# mechanical.net
KiCad netlist of a schematic drawn in Altium Designer
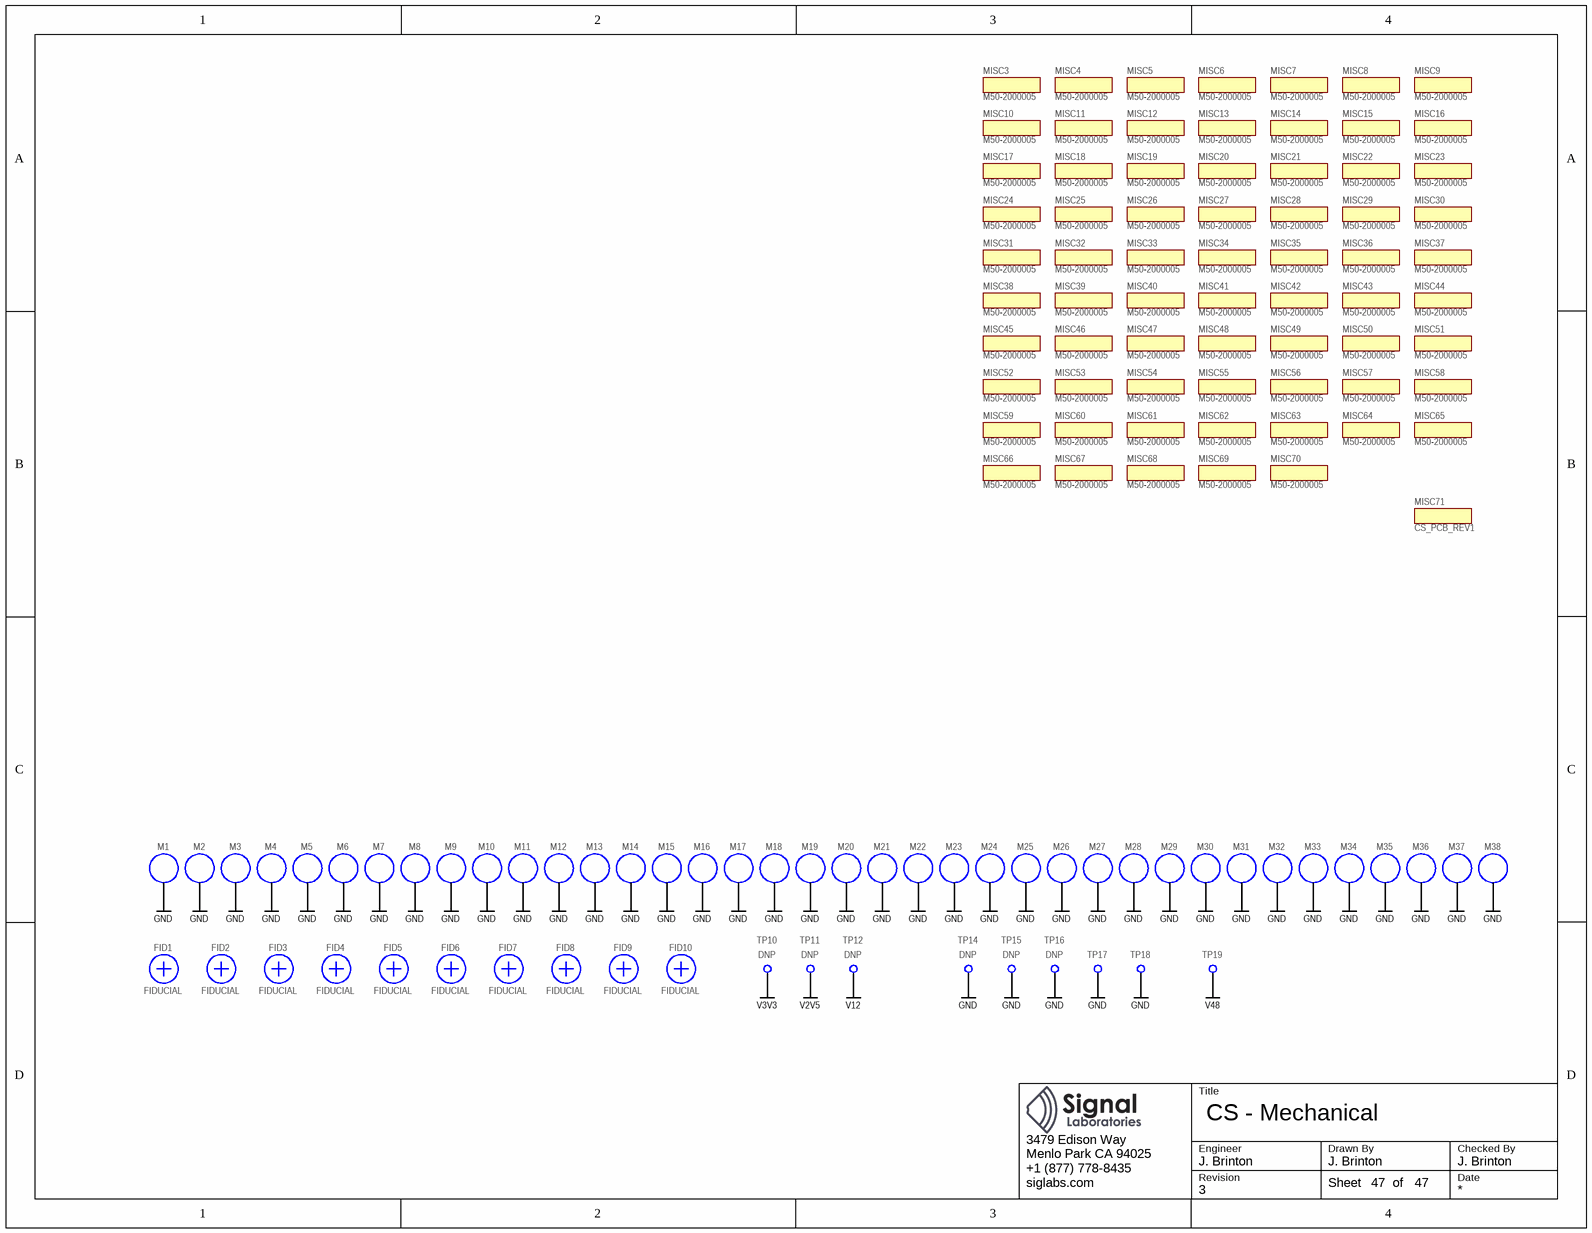
[diagram p0: mechanical.SchDoc]

(export (version "E")
  (design (tool "Eeschema 10.0.6"))
  (components
    (comp (ref "FID1")
      (value "FIDUCIAL")
      (footprint "FIDUCIAL")
      (libsource (lib "copper_suicide") (part "FIDUCIAL"))
    )
    (comp (ref "FID2")
      (value "FIDUCIAL")
      (footprint "FIDUCIAL")
      (libsource (lib "copper_suicide") (part "FIDUCIAL"))
    )
    (comp (ref "FID3")
      (value "FIDUCIAL")
      (footprint "FIDUCIAL")
      (libsource (lib "copper_suicide") (part "FIDUCIAL"))
    )
    (comp (ref "FID4")
      (value "FIDUCIAL")
      (footprint "FIDUCIAL")
      (libsource (lib "copper_suicide") (part "FIDUCIAL"))
    )
    (comp (ref "FID5")
      (value "FIDUCIAL")
      (footprint "FIDUCIAL")
      (libsource (lib "copper_suicide") (part "FIDUCIAL"))
    )
    (comp (ref "FID6")
      (value "FIDUCIAL")
      (footprint "FIDUCIAL")
      (libsource (lib "copper_suicide") (part "FIDUCIAL"))
    )
    (comp (ref "FID7")
      (value "FIDUCIAL")
      (footprint "FIDUCIAL")
      (libsource (lib "copper_suicide") (part "FIDUCIAL"))
    )
    (comp (ref "FID8")
      (value "FIDUCIAL")
      (footprint "FIDUCIAL")
      (libsource (lib "copper_suicide") (part "FIDUCIAL"))
    )
    (comp (ref "FID9")
      (value "FIDUCIAL")
      (footprint "FIDUCIAL")
      (libsource (lib "copper_suicide") (part "FIDUCIAL"))
    )
    (comp (ref "FID10")
      (value "FIDUCIAL")
      (footprint "FIDUCIAL")
      (libsource (lib "copper_suicide") (part "FIDUCIAL"))
    )
    (comp (ref "M1")
      (value "MOUNT")
      (footprint "MOUNTM3")
      (description "M3 Standard Fit Hole")
      (libsource (lib "copper_suicide") (part "MOUNT"))
    )
    (comp (ref "M2")
      (value "MOUNT")
      (footprint "MOUNTM3")
      (description "M3 Standard Fit Hole")
      (libsource (lib "copper_suicide") (part "MOUNT"))
    )
    (comp (ref "M3")
      (value "MOUNT")
      (footprint "MOUNTM3")
      (description "M3 Standard Fit Hole")
      (libsource (lib "copper_suicide") (part "MOUNT"))
    )
    (comp (ref "M4")
      (value "MOUNT")
      (footprint "MOUNTM3")
      (description "M3 Standard Fit Hole")
      (libsource (lib "copper_suicide") (part "MOUNT"))
    )
    (comp (ref "M5")
      (value "MOUNT")
      (footprint "MOUNTM3")
      (description "M3 Standard Fit Hole")
      (libsource (lib "copper_suicide") (part "MOUNT"))
    )
    (comp (ref "M6")
      (value "MOUNT")
      (footprint "MOUNTM3")
      (description "M3 Standard Fit Hole")
      (libsource (lib "copper_suicide") (part "MOUNT"))
    )
    (comp (ref "M7")
      (value "MOUNT")
      (footprint "MOUNTM3")
      (description "M3 Standard Fit Hole")
      (libsource (lib "copper_suicide") (part "MOUNT"))
    )
    (comp (ref "M8")
      (value "MOUNT")
      (footprint "MOUNTM3")
      (description "M3 Standard Fit Hole")
      (libsource (lib "copper_suicide") (part "MOUNT"))
    )
    (comp (ref "M9")
      (value "MOUNT")
      (footprint "MOUNTM3")
      (description "M3 Standard Fit Hole")
      (libsource (lib "copper_suicide") (part "MOUNT"))
    )
    (comp (ref "M10")
      (value "MOUNT")
      (footprint "MOUNTM3")
      (description "M3 Standard Fit Hole")
      (libsource (lib "copper_suicide") (part "MOUNT"))
    )
    (comp (ref "M11")
      (value "MOUNT")
      (footprint "MOUNTM3")
      (description "M3 Standard Fit Hole")
      (libsource (lib "copper_suicide") (part "MOUNT"))
    )
    (comp (ref "M12")
      (value "MOUNT")
      (footprint "MOUNTM3")
      (description "M3 Standard Fit Hole")
      (libsource (lib "copper_suicide") (part "MOUNT"))
    )
    (comp (ref "M13")
      (value "MOUNT")
      (footprint "MOUNTM3")
      (description "M3 Standard Fit Hole")
      (libsource (lib "copper_suicide") (part "MOUNT"))
    )
    (comp (ref "M14")
      (value "MOUNT")
      (footprint "MOUNTM3")
      (description "M3 Standard Fit Hole")
      (libsource (lib "copper_suicide") (part "MOUNT"))
    )
    (comp (ref "M15")
      (value "MOUNT")
      (footprint "MOUNTM3")
      (description "M3 Standard Fit Hole")
      (libsource (lib "copper_suicide") (part "MOUNT"))
    )
    (comp (ref "M16")
      (value "MOUNT")
      (footprint "MOUNTM3")
      (description "M3 Standard Fit Hole")
      (libsource (lib "copper_suicide") (part "MOUNT"))
    )
    (comp (ref "M17")
      (value "MOUNT")
      (footprint "MOUNTM3")
      (description "M3 Standard Fit Hole")
      (libsource (lib "copper_suicide") (part "MOUNT"))
    )
    (comp (ref "M18")
      (value "MOUNT")
      (footprint "MOUNTM3")
      (description "M3 Standard Fit Hole")
      (libsource (lib "copper_suicide") (part "MOUNT"))
    )
    (comp (ref "M19")
      (value "MOUNT")
      (footprint "MOUNTM3")
      (description "M3 Standard Fit Hole")
      (libsource (lib "copper_suicide") (part "MOUNT"))
    )
    (comp (ref "M20")
      (value "MOUNT")
      (footprint "MOUNTM3")
      (description "M3 Standard Fit Hole")
      (libsource (lib "copper_suicide") (part "MOUNT"))
    )
    (comp (ref "M21")
      (value "MOUNT")
      (footprint "MOUNTM3")
      (description "M3 Standard Fit Hole")
      (libsource (lib "copper_suicide") (part "MOUNT"))
    )
    (comp (ref "M22")
      (value "MOUNT")
      (footprint "MOUNTM3")
      (description "M3 Standard Fit Hole")
      (libsource (lib "copper_suicide") (part "MOUNT"))
    )
    (comp (ref "M23")
      (value "MOUNT")
      (footprint "MOUNTM3")
      (description "M3 Standard Fit Hole")
      (libsource (lib "copper_suicide") (part "MOUNT"))
    )
    (comp (ref "M24")
      (value "MOUNT")
      (footprint "MOUNTM3")
      (description "M3 Standard Fit Hole")
      (libsource (lib "copper_suicide") (part "MOUNT"))
    )
    (comp (ref "M25")
      (value "MOUNT")
      (footprint "MOUNTM3")
      (description "M3 Standard Fit Hole")
      (libsource (lib "copper_suicide") (part "MOUNT"))
    )
    (comp (ref "M26")
      (value "MOUNT")
      (footprint "MOUNTM3")
      (description "M3 Standard Fit Hole")
      (libsource (lib "copper_suicide") (part "MOUNT"))
    )
    (comp (ref "M27")
      (value "MOUNT")
      (footprint "MOUNTM3")
      (description "M3 Standard Fit Hole")
      (libsource (lib "copper_suicide") (part "MOUNT"))
    )
    (comp (ref "M28")
      (value "MOUNT")
      (footprint "MOUNTM3")
      (description "M3 Standard Fit Hole")
      (libsource (lib "copper_suicide") (part "MOUNT"))
    )
    (comp (ref "M29")
      (value "MOUNT")
      (footprint "MOUNTM3")
      (description "M3 Standard Fit Hole")
      (libsource (lib "copper_suicide") (part "MOUNT"))
    )
    (comp (ref "M30")
      (value "MOUNT")
      (footprint "MOUNTM3")
      (description "M3 Standard Fit Hole")
      (libsource (lib "copper_suicide") (part "MOUNT"))
    )
    (comp (ref "M31")
      (value "MOUNT")
      (footprint "MOUNTM3")
      (description "M3 Standard Fit Hole")
      (libsource (lib "copper_suicide") (part "MOUNT"))
    )
    (comp (ref "M32")
      (value "MOUNT")
      (footprint "MOUNTM3")
      (description "M3 Standard Fit Hole")
      (libsource (lib "copper_suicide") (part "MOUNT"))
    )
    (comp (ref "M33")
      (value "MOUNT")
      (footprint "MOUNTM3")
      (description "M3 Standard Fit Hole")
      (libsource (lib "copper_suicide") (part "MOUNT"))
    )
    (comp (ref "M34")
      (value "MOUNT")
      (footprint "MOUNTM3")
      (description "M3 Standard Fit Hole")
      (libsource (lib "copper_suicide") (part "MOUNT"))
    )
    (comp (ref "M35")
      (value "MOUNT")
      (footprint "MOUNTM3")
      (description "M3 Standard Fit Hole")
      (libsource (lib "copper_suicide") (part "MOUNT"))
    )
    (comp (ref "M36")
      (value "MOUNT")
      (footprint "MOUNTM3")
      (description "M3 Standard Fit Hole")
      (libsource (lib "copper_suicide") (part "MOUNT"))
    )
    (comp (ref "M37")
      (value "MOUNT")
      (footprint "MOUNTM3")
      (description "M3 Standard Fit Hole")
      (libsource (lib "copper_suicide") (part "MOUNT"))
    )
    (comp (ref "M38")
      (value "MOUNT")
      (footprint "MOUNTM3")
      (description "M3 Standard Fit Hole")
      (libsource (lib "copper_suicide") (part "MOUNT"))
    )
    (comp (ref "MISC3")
      (value "M50-2000005")
      (description "1.27mm Jumper Socket")
      (fields (field (name "MANUFACTURER") "Harwin"))
      (libsource (lib "harwin") (part "M50-1900005"))
    )
    (comp (ref "MISC4")
      (value "M50-2000005")
      (description "1.27mm Jumper Socket")
      (fields (field (name "MANUFACTURER") "Harwin"))
      (libsource (lib "harwin") (part "M50-1900005"))
    )
    (comp (ref "MISC5")
      (value "M50-2000005")
      (description "1.27mm Jumper Socket")
      (fields (field (name "MANUFACTURER") "Harwin"))
      (libsource (lib "harwin") (part "M50-1900005"))
    )
    (comp (ref "MISC6")
      (value "M50-2000005")
      (description "1.27mm Jumper Socket")
      (fields (field (name "MANUFACTURER") "Harwin"))
      (libsource (lib "harwin") (part "M50-1900005"))
    )
    (comp (ref "MISC7")
      (value "M50-2000005")
      (description "1.27mm Jumper Socket")
      (fields (field (name "MANUFACTURER") "Harwin"))
      (libsource (lib "harwin") (part "M50-1900005"))
    )
    (comp (ref "MISC8")
      (value "M50-2000005")
      (description "1.27mm Jumper Socket")
      (fields (field (name "MANUFACTURER") "Harwin"))
      (libsource (lib "harwin") (part "M50-1900005"))
    )
    (comp (ref "MISC9")
      (value "M50-2000005")
      (description "1.27mm Jumper Socket")
      (fields (field (name "MANUFACTURER") "Harwin"))
      (libsource (lib "harwin") (part "M50-1900005"))
    )
    (comp (ref "MISC10")
      (value "M50-2000005")
      (description "1.27mm Jumper Socket")
      (fields (field (name "MANUFACTURER") "Harwin"))
      (libsource (lib "harwin") (part "M50-1900005"))
    )
    (comp (ref "MISC11")
      (value "M50-2000005")
      (description "1.27mm Jumper Socket")
      (fields (field (name "MANUFACTURER") "Harwin"))
      (libsource (lib "harwin") (part "M50-1900005"))
    )
    (comp (ref "MISC12")
      (value "M50-2000005")
      (description "1.27mm Jumper Socket")
      (fields (field (name "MANUFACTURER") "Harwin"))
      (libsource (lib "harwin") (part "M50-1900005"))
    )
    (comp (ref "MISC13")
      (value "M50-2000005")
      (description "1.27mm Jumper Socket")
      (fields (field (name "MANUFACTURER") "Harwin"))
      (libsource (lib "harwin") (part "M50-1900005"))
    )
    (comp (ref "MISC14")
      (value "M50-2000005")
      (description "1.27mm Jumper Socket")
      (fields (field (name "MANUFACTURER") "Harwin"))
      (libsource (lib "harwin") (part "M50-1900005"))
    )
    (comp (ref "MISC15")
      (value "M50-2000005")
      (description "1.27mm Jumper Socket")
      (fields (field (name "MANUFACTURER") "Harwin"))
      (libsource (lib "harwin") (part "M50-1900005"))
    )
    (comp (ref "MISC16")
      (value "M50-2000005")
      (description "1.27mm Jumper Socket")
      (fields (field (name "MANUFACTURER") "Harwin"))
      (libsource (lib "harwin") (part "M50-1900005"))
    )
    (comp (ref "MISC17")
      (value "M50-2000005")
      (description "1.27mm Jumper Socket")
      (fields (field (name "MANUFACTURER") "Harwin"))
      (libsource (lib "harwin") (part "M50-1900005"))
    )
    (comp (ref "MISC18")
      (value "M50-2000005")
      (description "1.27mm Jumper Socket")
      (fields (field (name "MANUFACTURER") "Harwin"))
      (libsource (lib "harwin") (part "M50-1900005"))
    )
    (comp (ref "MISC19")
      (value "M50-2000005")
      (description "1.27mm Jumper Socket")
      (fields (field (name "MANUFACTURER") "Harwin"))
      (libsource (lib "harwin") (part "M50-1900005"))
    )
    (comp (ref "MISC20")
      (value "M50-2000005")
      (description "1.27mm Jumper Socket")
      (fields (field (name "MANUFACTURER") "Harwin"))
      (libsource (lib "harwin") (part "M50-1900005"))
    )
    (comp (ref "MISC21")
      (value "M50-2000005")
      (description "1.27mm Jumper Socket")
      (fields (field (name "MANUFACTURER") "Harwin"))
      (libsource (lib "harwin") (part "M50-1900005"))
    )
    (comp (ref "MISC22")
      (value "M50-2000005")
      (description "1.27mm Jumper Socket")
      (fields (field (name "MANUFACTURER") "Harwin"))
      (libsource (lib "harwin") (part "M50-1900005"))
    )
    (comp (ref "MISC23")
      (value "M50-2000005")
      (description "1.27mm Jumper Socket")
      (fields (field (name "MANUFACTURER") "Harwin"))
      (libsource (lib "harwin") (part "M50-1900005"))
    )
    (comp (ref "MISC24")
      (value "M50-2000005")
      (description "1.27mm Jumper Socket")
      (fields (field (name "MANUFACTURER") "Harwin"))
      (libsource (lib "harwin") (part "M50-1900005"))
    )
    (comp (ref "MISC25")
      (value "M50-2000005")
      (description "1.27mm Jumper Socket")
      (fields (field (name "MANUFACTURER") "Harwin"))
      (libsource (lib "harwin") (part "M50-1900005"))
    )
    (comp (ref "MISC26")
      (value "M50-2000005")
      (description "1.27mm Jumper Socket")
      (fields (field (name "MANUFACTURER") "Harwin"))
      (libsource (lib "harwin") (part "M50-1900005"))
    )
    (comp (ref "MISC27")
      (value "M50-2000005")
      (description "1.27mm Jumper Socket")
      (fields (field (name "MANUFACTURER") "Harwin"))
      (libsource (lib "harwin") (part "M50-1900005"))
    )
    (comp (ref "MISC28")
      (value "M50-2000005")
      (description "1.27mm Jumper Socket")
      (fields (field (name "MANUFACTURER") "Harwin"))
      (libsource (lib "harwin") (part "M50-1900005"))
    )
    (comp (ref "MISC29")
      (value "M50-2000005")
      (description "1.27mm Jumper Socket")
      (fields (field (name "MANUFACTURER") "Harwin"))
      (libsource (lib "harwin") (part "M50-1900005"))
    )
    (comp (ref "MISC30")
      (value "M50-2000005")
      (description "1.27mm Jumper Socket")
      (fields (field (name "MANUFACTURER") "Harwin"))
      (libsource (lib "harwin") (part "M50-1900005"))
    )
    (comp (ref "MISC31")
      (value "M50-2000005")
      (description "1.27mm Jumper Socket")
      (fields (field (name "MANUFACTURER") "Harwin"))
      (libsource (lib "harwin") (part "M50-1900005"))
    )
    (comp (ref "MISC32")
      (value "M50-2000005")
      (description "1.27mm Jumper Socket")
      (fields (field (name "MANUFACTURER") "Harwin"))
      (libsource (lib "harwin") (part "M50-1900005"))
    )
    (comp (ref "MISC33")
      (value "M50-2000005")
      (description "1.27mm Jumper Socket")
      (fields (field (name "MANUFACTURER") "Harwin"))
      (libsource (lib "harwin") (part "M50-1900005"))
    )
    (comp (ref "MISC34")
      (value "M50-2000005")
      (description "1.27mm Jumper Socket")
      (fields (field (name "MANUFACTURER") "Harwin"))
      (libsource (lib "harwin") (part "M50-1900005"))
    )
    (comp (ref "MISC35")
      (value "M50-2000005")
      (description "1.27mm Jumper Socket")
      (fields (field (name "MANUFACTURER") "Harwin"))
      (libsource (lib "harwin") (part "M50-1900005"))
    )
    (comp (ref "MISC36")
      (value "M50-2000005")
      (description "1.27mm Jumper Socket")
      (fields (field (name "MANUFACTURER") "Harwin"))
      (libsource (lib "harwin") (part "M50-1900005"))
    )
    (comp (ref "MISC37")
      (value "M50-2000005")
      (description "1.27mm Jumper Socket")
      (fields (field (name "MANUFACTURER") "Harwin"))
      (libsource (lib "harwin") (part "M50-1900005"))
    )
    (comp (ref "MISC38")
      (value "M50-2000005")
      (description "1.27mm Jumper Socket")
      (fields (field (name "MANUFACTURER") "Harwin"))
      (libsource (lib "harwin") (part "M50-1900005"))
    )
    (comp (ref "MISC39")
      (value "M50-2000005")
      (description "1.27mm Jumper Socket")
      (fields (field (name "MANUFACTURER") "Harwin"))
      (libsource (lib "harwin") (part "M50-1900005"))
    )
    (comp (ref "MISC40")
      (value "M50-2000005")
      (description "1.27mm Jumper Socket")
      (fields (field (name "MANUFACTURER") "Harwin"))
      (libsource (lib "harwin") (part "M50-1900005"))
    )
    (comp (ref "MISC41")
      (value "M50-2000005")
      (description "1.27mm Jumper Socket")
      (fields (field (name "MANUFACTURER") "Harwin"))
      (libsource (lib "harwin") (part "M50-1900005"))
    )
    (comp (ref "MISC42")
      (value "M50-2000005")
      (description "1.27mm Jumper Socket")
      (fields (field (name "MANUFACTURER") "Harwin"))
      (libsource (lib "harwin") (part "M50-1900005"))
    )
    (comp (ref "MISC43")
      (value "M50-2000005")
      (description "1.27mm Jumper Socket")
      (fields (field (name "MANUFACTURER") "Harwin"))
      (libsource (lib "harwin") (part "M50-1900005"))
    )
    (comp (ref "MISC44")
      (value "M50-2000005")
      (description "1.27mm Jumper Socket")
      (fields (field (name "MANUFACTURER") "Harwin"))
      (libsource (lib "harwin") (part "M50-1900005"))
    )
    (comp (ref "MISC45")
      (value "M50-2000005")
      (description "1.27mm Jumper Socket")
      (fields (field (name "MANUFACTURER") "Harwin"))
      (libsource (lib "harwin") (part "M50-1900005"))
    )
    (comp (ref "MISC46")
      (value "M50-2000005")
      (description "1.27mm Jumper Socket")
      (fields (field (name "MANUFACTURER") "Harwin"))
      (libsource (lib "harwin") (part "M50-1900005"))
    )
    (comp (ref "MISC47")
      (value "M50-2000005")
      (description "1.27mm Jumper Socket")
      (fields (field (name "MANUFACTURER") "Harwin"))
      (libsource (lib "harwin") (part "M50-1900005"))
    )
    (comp (ref "MISC48")
      (value "M50-2000005")
      (description "1.27mm Jumper Socket")
      (fields (field (name "MANUFACTURER") "Harwin"))
      (libsource (lib "harwin") (part "M50-1900005"))
    )
    (comp (ref "MISC49")
      (value "M50-2000005")
      (description "1.27mm Jumper Socket")
      (fields (field (name "MANUFACTURER") "Harwin"))
      (libsource (lib "harwin") (part "M50-1900005"))
    )
    (comp (ref "MISC50")
      (value "M50-2000005")
      (description "1.27mm Jumper Socket")
      (fields (field (name "MANUFACTURER") "Harwin"))
      (libsource (lib "harwin") (part "M50-1900005"))
    )
    (comp (ref "MISC51")
      (value "M50-2000005")
      (description "1.27mm Jumper Socket")
      (fields (field (name "MANUFACTURER") "Harwin"))
      (libsource (lib "harwin") (part "M50-1900005"))
    )
    (comp (ref "MISC52")
      (value "M50-2000005")
      (description "1.27mm Jumper Socket")
      (fields (field (name "MANUFACTURER") "Harwin"))
      (libsource (lib "harwin") (part "M50-1900005"))
    )
    (comp (ref "MISC53")
      (value "M50-2000005")
      (description "1.27mm Jumper Socket")
      (fields (field (name "MANUFACTURER") "Harwin"))
      (libsource (lib "harwin") (part "M50-1900005"))
    )
    (comp (ref "MISC54")
      (value "M50-2000005")
      (description "1.27mm Jumper Socket")
      (fields (field (name "MANUFACTURER") "Harwin"))
      (libsource (lib "harwin") (part "M50-1900005"))
    )
    (comp (ref "MISC55")
      (value "M50-2000005")
      (description "1.27mm Jumper Socket")
      (fields (field (name "MANUFACTURER") "Harwin"))
      (libsource (lib "harwin") (part "M50-1900005"))
    )
    (comp (ref "MISC56")
      (value "M50-2000005")
      (description "1.27mm Jumper Socket")
      (fields (field (name "MANUFACTURER") "Harwin"))
      (libsource (lib "harwin") (part "M50-1900005"))
    )
    (comp (ref "MISC57")
      (value "M50-2000005")
      (description "1.27mm Jumper Socket")
      (fields (field (name "MANUFACTURER") "Harwin"))
      (libsource (lib "harwin") (part "M50-1900005"))
    )
    (comp (ref "MISC58")
      (value "M50-2000005")
      (description "1.27mm Jumper Socket")
      (fields (field (name "MANUFACTURER") "Harwin"))
      (libsource (lib "harwin") (part "M50-1900005"))
    )
    (comp (ref "MISC59")
      (value "M50-2000005")
      (description "1.27mm Jumper Socket")
      (fields (field (name "MANUFACTURER") "Harwin"))
      (libsource (lib "harwin") (part "M50-1900005"))
    )
    (comp (ref "MISC60")
      (value "M50-2000005")
      (description "1.27mm Jumper Socket")
      (fields (field (name "MANUFACTURER") "Harwin"))
      (libsource (lib "harwin") (part "M50-1900005"))
    )
    (comp (ref "MISC61")
      (value "M50-2000005")
      (description "1.27mm Jumper Socket")
      (fields (field (name "MANUFACTURER") "Harwin"))
      (libsource (lib "harwin") (part "M50-1900005"))
    )
    (comp (ref "MISC62")
      (value "M50-2000005")
      (description "1.27mm Jumper Socket")
      (fields (field (name "MANUFACTURER") "Harwin"))
      (libsource (lib "harwin") (part "M50-1900005"))
    )
    (comp (ref "MISC63")
      (value "M50-2000005")
      (description "1.27mm Jumper Socket")
      (fields (field (name "MANUFACTURER") "Harwin"))
      (libsource (lib "harwin") (part "M50-1900005"))
    )
    (comp (ref "MISC64")
      (value "M50-2000005")
      (description "1.27mm Jumper Socket")
      (fields (field (name "MANUFACTURER") "Harwin"))
      (libsource (lib "harwin") (part "M50-1900005"))
    )
    (comp (ref "MISC65")
      (value "M50-2000005")
      (description "1.27mm Jumper Socket")
      (fields (field (name "MANUFACTURER") "Harwin"))
      (libsource (lib "harwin") (part "M50-1900005"))
    )
    (comp (ref "MISC66")
      (value "M50-2000005")
      (description "1.27mm Jumper Socket")
      (fields (field (name "MANUFACTURER") "Harwin"))
      (libsource (lib "harwin") (part "M50-1900005"))
    )
    (comp (ref "MISC67")
      (value "M50-2000005")
      (description "1.27mm Jumper Socket")
      (fields (field (name "MANUFACTURER") "Harwin"))
      (libsource (lib "harwin") (part "M50-1900005"))
    )
    (comp (ref "MISC68")
      (value "M50-2000005")
      (description "1.27mm Jumper Socket")
      (fields (field (name "MANUFACTURER") "Harwin"))
      (libsource (lib "harwin") (part "M50-1900005"))
    )
    (comp (ref "MISC69")
      (value "M50-2000005")
      (description "1.27mm Jumper Socket")
      (fields (field (name "MANUFACTURER") "Harwin"))
      (libsource (lib "harwin") (part "M50-1900005"))
    )
    (comp (ref "MISC70")
      (value "M50-2000005")
      (description "1.27mm Jumper Socket")
      (fields (field (name "MANUFACTURER") "Harwin"))
      (libsource (lib "harwin") (part "M50-1900005"))
    )
    (comp (ref "MISC71")
      (value "CS_PCB_REV1")
      (description "Copper Suicide PCB")
      (fields (field (name "MANUFACTURER") "Signal Laboratories, Inc."))
      (libsource (lib "harwin") (part "M50-1900005"))
    )
    (comp (ref "TP10")
      (value "5000")
      (footprint "TEST_POINT")
      (description "Thruhole Miniature Test Point")
      (fields (field (name "MANUFACTURER") "Keystone Electronics Corp") (field (name "DO NOT PLACE") "DNP"))
      (libsource (lib "generic") (part "TEST_POINT"))
    )
    (comp (ref "TP11")
      (value "5000")
      (footprint "TEST_POINT")
      (description "Thruhole Miniature Test Point")
      (fields (field (name "MANUFACTURER") "Keystone Electronics Corp") (field (name "DO NOT PLACE") "DNP"))
      (libsource (lib "generic") (part "TEST_POINT"))
    )
    (comp (ref "TP12")
      (value "5000")
      (footprint "TEST_POINT")
      (description "Thruhole Miniature Test Point")
      (fields (field (name "MANUFACTURER") "Keystone Electronics Corp") (field (name "DO NOT PLACE") "DNP"))
      (libsource (lib "generic") (part "TEST_POINT"))
    )
    (comp (ref "TP14")
      (value "5000")
      (footprint "TEST_POINT")
      (description "Thruhole Miniature Test Point")
      (fields (field (name "MANUFACTURER") "Keystone Electronics Corp") (field (name "DO NOT PLACE") "DNP"))
      (libsource (lib "generic") (part "TEST_POINT"))
    )
    (comp (ref "TP15")
      (value "5000")
      (footprint "TEST_POINT")
      (description "Thruhole Miniature Test Point")
      (fields (field (name "MANUFACTURER") "Keystone Electronics Corp") (field (name "DO NOT PLACE") "DNP"))
      (libsource (lib "generic") (part "TEST_POINT"))
    )
    (comp (ref "TP16")
      (value "5000")
      (footprint "TEST_POINT")
      (description "Thruhole Miniature Test Point")
      (fields (field (name "MANUFACTURER") "Keystone Electronics Corp") (field (name "DO NOT PLACE") "DNP"))
      (libsource (lib "generic") (part "TEST_POINT"))
    )
    (comp (ref "TP17")
      (value "5000")
      (footprint "TEST_POINT")
      (description "Thruhole Miniature Test Point")
      (fields (field (name "MANUFACTURER") "Keystone Electronics Corp"))
      (libsource (lib "generic") (part "TEST_POINT"))
    )
    (comp (ref "TP18")
      (value "5000")
      (footprint "TEST_POINT")
      (description "Thruhole Miniature Test Point")
      (fields (field (name "MANUFACTURER") "Keystone Electronics Corp"))
      (libsource (lib "generic") (part "TEST_POINT"))
    )
    (comp (ref "TP19")
      (value "5000")
      (footprint "TEST_POINT")
      (description "Thruhole Miniature Test Point")
      (fields (field (name "MANUFACTURER") "Keystone Electronics Corp"))
      (libsource (lib "generic") (part "TEST_POINT"))
    )
  )
  (nets
    (net (code "1") (name "GND") (class "Default")
      (node (ref "M1") (pin "1") (pinfunction "MNT_1") (pintype "passive"))
      (node (ref "M10") (pin "1") (pinfunction "MNT_1") (pintype "passive"))
      (node (ref "M11") (pin "1") (pinfunction "MNT_1") (pintype "passive"))
      (node (ref "M12") (pin "1") (pinfunction "MNT_1") (pintype "passive"))
      (node (ref "M13") (pin "1") (pinfunction "MNT_1") (pintype "passive"))
      (node (ref "M14") (pin "1") (pinfunction "MNT_1") (pintype "passive"))
      (node (ref "M15") (pin "1") (pinfunction "MNT_1") (pintype "passive"))
      (node (ref "M16") (pin "1") (pinfunction "MNT_1") (pintype "passive"))
      (node (ref "M17") (pin "1") (pinfunction "MNT_1") (pintype "passive"))
      (node (ref "M18") (pin "1") (pinfunction "MNT_1") (pintype "passive"))
      (node (ref "M19") (pin "1") (pinfunction "MNT_1") (pintype "passive"))
      (node (ref "M2") (pin "1") (pinfunction "MNT_1") (pintype "passive"))
      (node (ref "M20") (pin "1") (pinfunction "MNT_1") (pintype "passive"))
      (node (ref "M21") (pin "1") (pinfunction "MNT_1") (pintype "passive"))
      (node (ref "M22") (pin "1") (pinfunction "MNT_1") (pintype "passive"))
      (node (ref "M23") (pin "1") (pinfunction "MNT_1") (pintype "passive"))
      (node (ref "M24") (pin "1") (pinfunction "MNT_1") (pintype "passive"))
      (node (ref "M25") (pin "1") (pinfunction "MNT_1") (pintype "passive"))
      (node (ref "M26") (pin "1") (pinfunction "MNT_1") (pintype "passive"))
      (node (ref "M27") (pin "1") (pinfunction "MNT_1") (pintype "passive"))
      (node (ref "M28") (pin "1") (pinfunction "MNT_1") (pintype "passive"))
      (node (ref "M29") (pin "1") (pinfunction "MNT_1") (pintype "passive"))
      (node (ref "M3") (pin "1") (pinfunction "MNT_1") (pintype "passive"))
      (node (ref "M30") (pin "1") (pinfunction "MNT_1") (pintype "passive"))
      (node (ref "M31") (pin "1") (pinfunction "MNT_1") (pintype "passive"))
      (node (ref "M32") (pin "1") (pinfunction "MNT_1") (pintype "passive"))
      (node (ref "M33") (pin "1") (pinfunction "MNT_1") (pintype "passive"))
      (node (ref "M34") (pin "1") (pinfunction "MNT_1") (pintype "passive"))
      (node (ref "M35") (pin "1") (pinfunction "MNT_1") (pintype "passive"))
      (node (ref "M36") (pin "1") (pinfunction "MNT_1") (pintype "passive"))
      (node (ref "M37") (pin "1") (pinfunction "MNT_1") (pintype "passive"))
      (node (ref "M38") (pin "1") (pinfunction "MNT_1") (pintype "passive"))
      (node (ref "M4") (pin "1") (pinfunction "MNT_1") (pintype "passive"))
      (node (ref "M5") (pin "1") (pinfunction "MNT_1") (pintype "passive"))
      (node (ref "M6") (pin "1") (pinfunction "MNT_1") (pintype "passive"))
      (node (ref "M7") (pin "1") (pinfunction "MNT_1") (pintype "passive"))
      (node (ref "M8") (pin "1") (pinfunction "MNT_1") (pintype "passive"))
      (node (ref "M9") (pin "1") (pinfunction "MNT_1") (pintype "passive"))
      (node (ref "TP14") (pin "1") (pinfunction "1_1") (pintype "passive"))
      (node (ref "TP15") (pin "1") (pinfunction "1_1") (pintype "passive"))
      (node (ref "TP16") (pin "1") (pinfunction "1_1") (pintype "passive"))
      (node (ref "TP17") (pin "1") (pinfunction "1_1") (pintype "passive"))
      (node (ref "TP18") (pin "1") (pinfunction "1_1") (pintype "passive"))
    )
    (net (code "2") (name "V2V5") (class "Default")
      (node (ref "TP11") (pin "1") (pinfunction "1_1") (pintype "passive"))
    )
    (net (code "3") (name "V3V3") (class "Default")
      (node (ref "TP10") (pin "1") (pinfunction "1_1") (pintype "passive"))
    )
    (net (code "4") (name "V12") (class "Default")
      (node (ref "TP12") (pin "1") (pinfunction "1_1") (pintype "passive"))
    )
    (net (code "5") (name "V48") (class "Default")
      (node (ref "TP19") (pin "1") (pinfunction "1_1") (pintype "passive"))
    )
  )
)
